# working.net
KiCad netlist of a schematic drawn in EAGLE
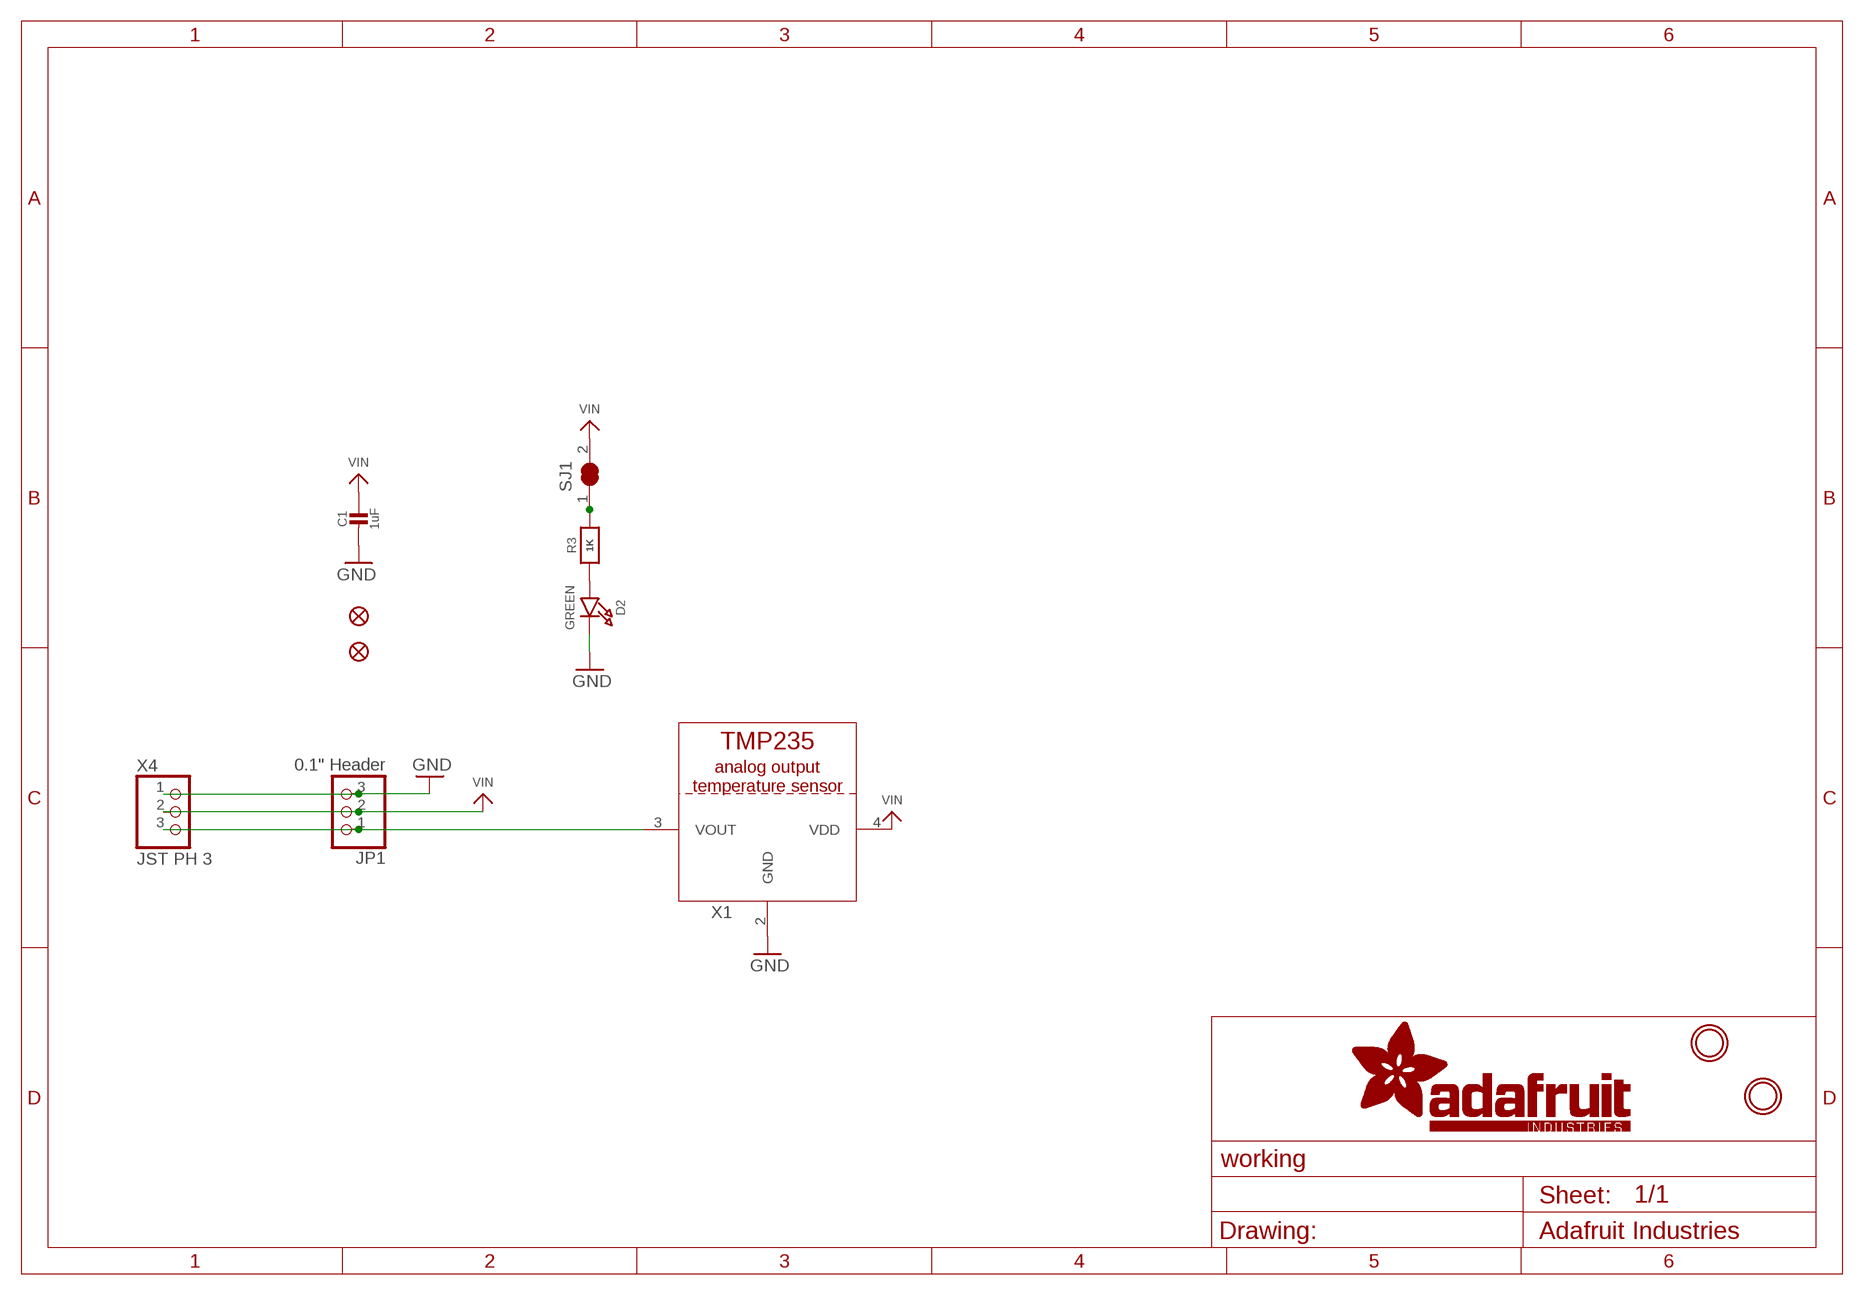
[diagram p0: schematic, sheet 1]

(export (version "E")
  (design (tool "Eeschema 10.0.6"))
  (components
    (comp (ref "C1")
      (value "1uF")
      (footprint "eagle-import:0805-NO")
      (libsource (lib "eagle-import") (part "CAP_CERAMIC0805-NOOUTLINE"))
    )
    (comp (ref "D2")
      (value "GREEN")
      (footprint "eagle-import:CHIPLED_0805_NOOUTLINE")
      (libsource (lib "eagle-import") (part "LED0805_NOOUTLINE"))
    )
    (comp (ref "FID2")
      (value "FIDUCIAL_1MM")
      (footprint "eagle-import:FIDUCIAL_1MM")
      (libsource (lib "eagle-import") (part "FIDUCIAL_1MM"))
    )
    (comp (ref "FID3")
      (value "FIDUCIAL_1MM")
      (footprint "eagle-import:FIDUCIAL_1MM")
      (libsource (lib "eagle-import") (part "FIDUCIAL_1MM"))
    )
    (comp (ref "JP1")
      (value "0.1\" Header")
      (footprint "eagle-import:1X03_OVAL")
      (libsource (lib "eagle-import") (part "HEADER-1X3"))
    )
    (comp (ref "R3")
      (value "1K")
      (footprint "eagle-import:0603-NO")
      (libsource (lib "eagle-import") (part "RESISTOR_0603_NOOUT"))
    )
    (comp (ref "SJ1")
      (value "SOLDERJUMPER_CLOSED")
      (footprint "eagle-import:SOLDERJUMPER_CLOSEDWIRE")
      (libsource (lib "eagle-import") (part "SOLDERJUMPER_CLOSED"))
    )
    (comp (ref "U$1")
      (value "MOUNTINGHOLE2.5")
      (footprint "eagle-import:MOUNTINGHOLE_2.5_PLATED")
      (libsource (lib "eagle-import") (part "MOUNTINGHOLE2.5"))
    )
    (comp (ref "U$8")
      (value "MOUNTINGHOLE2.5")
      (footprint "eagle-import:MOUNTINGHOLE_2.5_PLATED")
      (libsource (lib "eagle-import") (part "MOUNTINGHOLE2.5"))
    )
    (comp (ref "X1")
      (value "TMP235_DCKR")
      (footprint "eagle-import:SC70-5")
      (libsource (lib "eagle-import") (part "TMP235_DCKR"))
    )
    (comp (ref "X4")
      (value "JST PH 3")
      (footprint "eagle-import:JSTPH3")
      (libsource (lib "eagle-import") (part "CON_JST_PH_3PIN"))
    )
  )
  (nets
    (net (code "1") (name "GND") (class "Default")
      (node (ref "C1") (pin "2") (pinfunction "2_2") (pintype "passive"))
      (node (ref "D2") (pin "C") (pinfunction "C_C") (pintype "passive"))
      (node (ref "JP1") (pin "3") (pinfunction "3_3") (pintype "passive"))
      (node (ref "X1") (pin "2") (pinfunction "GND_2") (pintype "power_in"))
      (node (ref "X4") (pin "1") (pinfunction "1_1") (pintype "passive"))
    )
    (net (code "2") (name "Net-(D2-PadA)") (class "Default")
      (node (ref "D2") (pin "A") (pinfunction "A_A") (pintype "passive"))
      (node (ref "R3") (pin "1") (pinfunction "1_1") (pintype "passive"))
    )
    (net (code "3") (name "Net-(R3-Pad2)") (class "Default")
      (node (ref "R3") (pin "2") (pinfunction "2_2") (pintype "passive"))
      (node (ref "SJ1") (pin "1") (pinfunction "1_1") (pintype "passive"))
    )
    (net (code "4") (name "Net-(X1-VOUT)") (class "Default")
      (node (ref "JP1") (pin "1") (pinfunction "1_1") (pintype "passive"))
      (node (ref "X1") (pin "3") (pinfunction "VOUT_3") (pintype "output"))
      (node (ref "X4") (pin "3") (pinfunction "3_3") (pintype "passive"))
    )
    (net (code "5") (name "VIN") (class "Default")
      (node (ref "C1") (pin "1") (pinfunction "1_1") (pintype "passive"))
      (node (ref "JP1") (pin "2") (pinfunction "2_2") (pintype "passive"))
      (node (ref "SJ1") (pin "2") (pinfunction "2_2") (pintype "passive"))
      (node (ref "X1") (pin "4") (pinfunction "VDD_4") (pintype "power_in"))
      (node (ref "X4") (pin "2") (pinfunction "2_2") (pintype "passive"))
    )
  )
)
